# ESC-combined.net
KiCad netlist of a schematic drawn in EAGLE
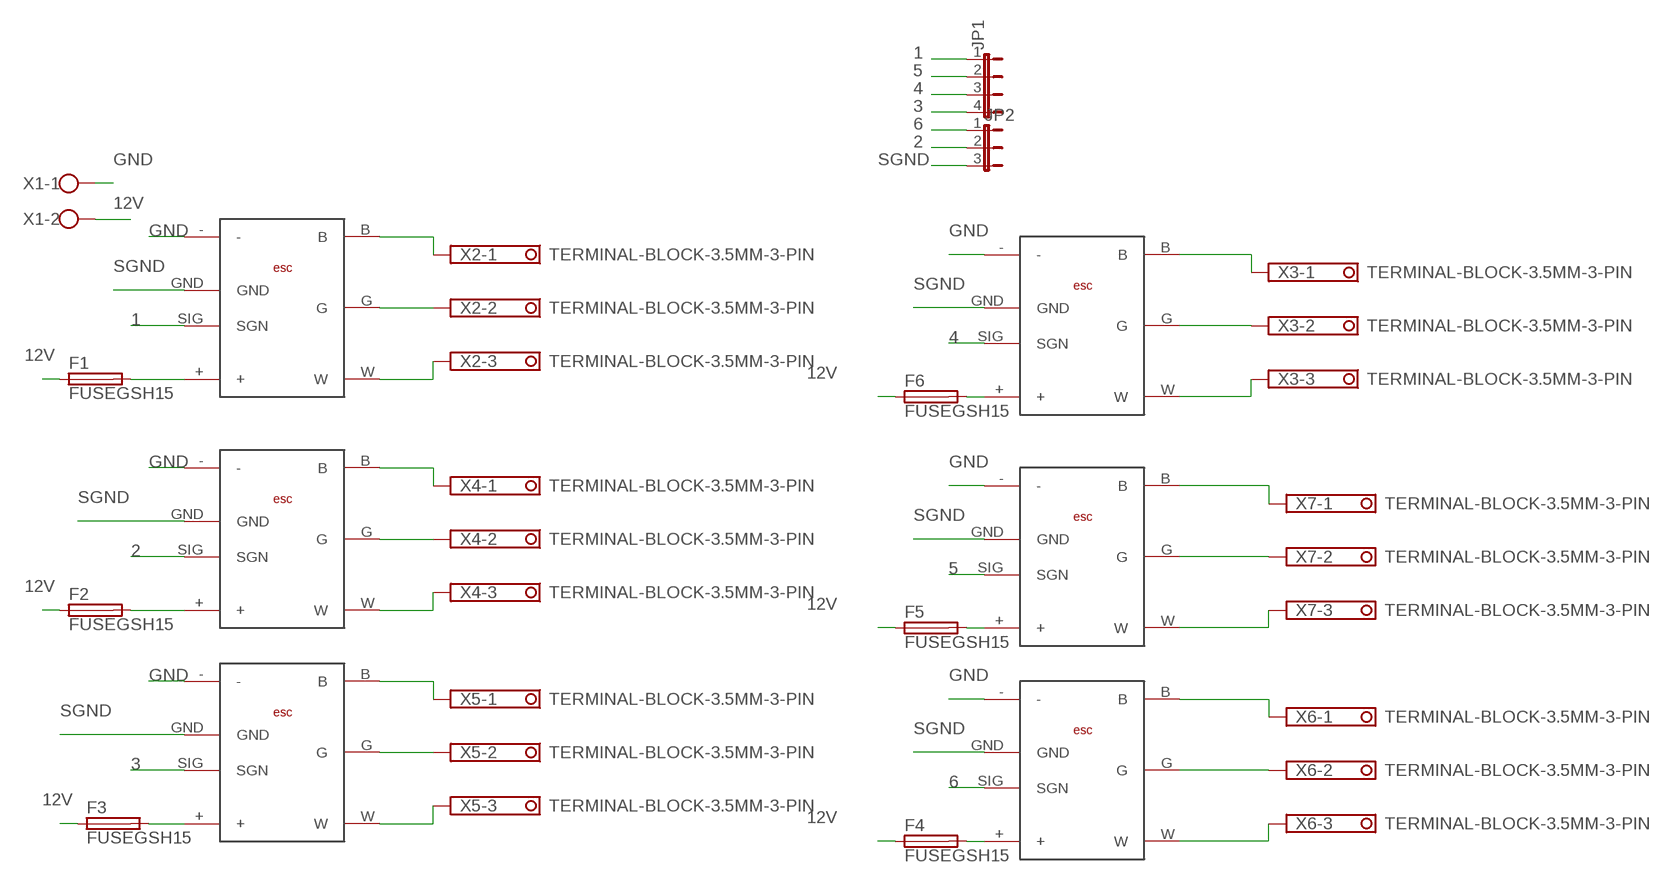
[diagram p0: schematic, sheet 1]

(export (version "E")
  (design (tool "Eeschema 10.0.6"))
  (components
    (comp (ref "F1")
      (value "FUSEGSH15")
      (footprint "eagle-import:GSH15")
      (libsource (lib "eagle-import") (part "FUSEGSH15"))
    )
    (comp (ref "F2")
      (value "FUSEGSH15")
      (footprint "eagle-import:GSH15")
      (libsource (lib "eagle-import") (part "FUSEGSH15"))
    )
    (comp (ref "F3")
      (value "FUSEGSH15")
      (footprint "eagle-import:GSH15")
      (libsource (lib "eagle-import") (part "FUSEGSH15"))
    )
    (comp (ref "F4")
      (value "FUSEGSH15")
      (footprint "eagle-import:GSH15")
      (libsource (lib "eagle-import") (part "FUSEGSH15"))
    )
    (comp (ref "F5")
      (value "FUSEGSH15")
      (footprint "eagle-import:GSH15")
      (libsource (lib "eagle-import") (part "FUSEGSH15"))
    )
    (comp (ref "F6")
      (value "FUSEGSH15")
      (footprint "eagle-import:GSH15")
      (libsource (lib "eagle-import") (part "FUSEGSH15"))
    )
    (comp (ref "JP1")
      (value "JP4E")
      (footprint "eagle-import:JP4")
      (libsource (lib "eagle-import") (part "JP4E"))
    )
    (comp (ref "JP2")
      (value "JP2E")
      (footprint "eagle-import:JP2")
      (libsource (lib "eagle-import") (part "JP2E"))
    )
    (comp (ref "U$1")
      (value "ESCV!")
      (footprint "eagle-import:ESCV!")
      (libsource (lib "eagle-import") (part "ESCV!"))
    )
    (comp (ref "U$2")
      (value "ESCV!")
      (footprint "eagle-import:ESCV!")
      (libsource (lib "eagle-import") (part "ESCV!"))
    )
    (comp (ref "U$3")
      (value "ESCV!")
      (footprint "eagle-import:ESCV!")
      (libsource (lib "eagle-import") (part "ESCV!"))
    )
    (comp (ref "U$4")
      (value "ESCV!")
      (footprint "eagle-import:ESCV!")
      (libsource (lib "eagle-import") (part "ESCV!"))
    )
    (comp (ref "U$5")
      (value "ESCV!")
      (footprint "eagle-import:ESCV!")
      (libsource (lib "eagle-import") (part "ESCV!"))
    )
    (comp (ref "U$6")
      (value "ESCV!")
      (footprint "eagle-import:ESCV!")
      (libsource (lib "eagle-import") (part "ESCV!"))
    )
    (comp (ref "X1")
      (value "12V")
      (footprint "eagle-import:W237-102")
      (fields (field (name "MPN") "237-102"))
      (libsource (lib "eagle-import") (part "W237-102"))
    )
    (comp (ref "X2")
      (value "TERMINAL-BLOCK-3.5MM-3-PIN")
      (footprint "eagle-import:HDRV3W150P950_1X3_3150X1470X1860A")
      (libsource (lib "eagle-import") (part "TERMINAL-BLOCK-3.5MM-3-PIN"))
    )
    (comp (ref "X3")
      (value "TERMINAL-BLOCK-3.5MM-3-PIN")
      (footprint "eagle-import:HDRV3W150P950_1X3_3150X1470X1860A")
      (libsource (lib "eagle-import") (part "TERMINAL-BLOCK-3.5MM-3-PIN"))
    )
    (comp (ref "X4")
      (value "TERMINAL-BLOCK-3.5MM-3-PIN")
      (footprint "eagle-import:HDRV3W150P950_1X3_3150X1470X1860A")
      (libsource (lib "eagle-import") (part "TERMINAL-BLOCK-3.5MM-3-PIN"))
    )
    (comp (ref "X5")
      (value "TERMINAL-BLOCK-3.5MM-3-PIN")
      (footprint "eagle-import:HDRV3W150P950_1X3_3150X1470X1860A")
      (libsource (lib "eagle-import") (part "TERMINAL-BLOCK-3.5MM-3-PIN"))
    )
    (comp (ref "X6")
      (value "TERMINAL-BLOCK-3.5MM-3-PIN")
      (footprint "eagle-import:HDRV3W150P950_1X3_3150X1470X1860A")
      (libsource (lib "eagle-import") (part "TERMINAL-BLOCK-3.5MM-3-PIN"))
    )
    (comp (ref "X7")
      (value "TERMINAL-BLOCK-3.5MM-3-PIN")
      (footprint "eagle-import:HDRV3W150P950_1X3_3150X1470X1860A")
      (libsource (lib "eagle-import") (part "TERMINAL-BLOCK-3.5MM-3-PIN"))
    )
  )
  (nets
    (net (code "1") (name "/1") (class "Default")
      (node (ref "JP1") (pin "1") (pinfunction "1_1") (pintype "passive"))
      (node (ref "U$1") (pin "SIG") (pinfunction "SGN_SIG") (pintype "bidirectional"))
    )
    (net (code "2") (name "/2") (class "Default")
      (node (ref "JP2") (pin "2") (pinfunction "2_2") (pintype "passive"))
      (node (ref "U$2") (pin "SIG") (pinfunction "SGN_SIG") (pintype "bidirectional"))
    )
    (net (code "3") (name "/3") (class "Default")
      (node (ref "JP1") (pin "4") (pinfunction "4_4") (pintype "passive"))
      (node (ref "U$3") (pin "SIG") (pinfunction "SGN_SIG") (pintype "bidirectional"))
    )
    (net (code "4") (name "/4") (class "Default")
      (node (ref "JP1") (pin "3") (pinfunction "3_3") (pintype "passive"))
      (node (ref "U$4") (pin "SIG") (pinfunction "SGN_SIG") (pintype "bidirectional"))
    )
    (net (code "5") (name "/5") (class "Default")
      (node (ref "JP1") (pin "2") (pinfunction "2_2") (pintype "passive"))
      (node (ref "U$5") (pin "SIG") (pinfunction "SGN_SIG") (pintype "bidirectional"))
    )
    (net (code "6") (name "/6") (class "Default")
      (node (ref "JP2") (pin "1") (pinfunction "1_1") (pintype "passive"))
      (node (ref "U$6") (pin "SIG") (pinfunction "SGN_SIG") (pintype "bidirectional"))
    )
    (net (code "7") (name "/12V") (class "Default")
      (node (ref "F1") (pin "1") (pinfunction "1_1") (pintype "passive"))
      (node (ref "F2") (pin "1") (pinfunction "1_1") (pintype "passive"))
      (node (ref "F3") (pin "1") (pinfunction "1_1") (pintype "passive"))
      (node (ref "F4") (pin "1") (pinfunction "1_1") (pintype "passive"))
      (node (ref "F5") (pin "1") (pinfunction "1_1") (pintype "passive"))
      (node (ref "F6") (pin "1") (pinfunction "1_1") (pintype "passive"))
      (node (ref "X1") (pin "2") (pinfunction "KL_2") (pintype "passive"))
    )
    (net (code "8") (name "/GND") (class "Default")
      (node (ref "U$1") (pin "-") (pinfunction "-_-") (pintype "bidirectional"))
      (node (ref "U$2") (pin "-") (pinfunction "-_-") (pintype "bidirectional"))
      (node (ref "U$3") (pin "-") (pinfunction "-_-") (pintype "bidirectional"))
      (node (ref "U$4") (pin "-") (pinfunction "-_-") (pintype "bidirectional"))
      (node (ref "U$5") (pin "-") (pinfunction "-_-") (pintype "bidirectional"))
      (node (ref "U$6") (pin "-") (pinfunction "-_-") (pintype "bidirectional"))
      (node (ref "X1") (pin "1") (pinfunction "KL_1") (pintype "passive"))
    )
    (net (code "9") (name "/SGND") (class "Default")
      (node (ref "JP2") (pin "3") (pinfunction "3_3") (pintype "passive"))
      (node (ref "U$1") (pin "GND") (pinfunction "GND_GND") (pintype "bidirectional"))
      (node (ref "U$2") (pin "GND") (pinfunction "GND_GND") (pintype "bidirectional"))
      (node (ref "U$3") (pin "GND") (pinfunction "GND_GND") (pintype "bidirectional"))
      (node (ref "U$4") (pin "GND") (pinfunction "GND_GND") (pintype "bidirectional"))
      (node (ref "U$5") (pin "GND") (pinfunction "GND_GND") (pintype "bidirectional"))
      (node (ref "U$6") (pin "GND") (pinfunction "GND_GND") (pintype "bidirectional"))
    )
    (net (code "10") (name "Net-(F1-Pad2)") (class "Default")
      (node (ref "F1") (pin "2") (pinfunction "2_2") (pintype "passive"))
      (node (ref "U$1") (pin "+") (pinfunction "+_+") (pintype "bidirectional"))
    )
    (net (code "11") (name "Net-(F2-Pad2)") (class "Default")
      (node (ref "F2") (pin "2") (pinfunction "2_2") (pintype "passive"))
      (node (ref "U$2") (pin "+") (pinfunction "+_+") (pintype "bidirectional"))
    )
    (net (code "12") (name "Net-(F3-Pad2)") (class "Default")
      (node (ref "F3") (pin "2") (pinfunction "2_2") (pintype "passive"))
      (node (ref "U$3") (pin "+") (pinfunction "+_+") (pintype "bidirectional"))
    )
    (net (code "13") (name "Net-(F4-Pad2)") (class "Default")
      (node (ref "F4") (pin "2") (pinfunction "2_2") (pintype "passive"))
      (node (ref "U$6") (pin "+") (pinfunction "+_+") (pintype "bidirectional"))
    )
    (net (code "14") (name "Net-(F5-Pad2)") (class "Default")
      (node (ref "F5") (pin "2") (pinfunction "2_2") (pintype "passive"))
      (node (ref "U$5") (pin "+") (pinfunction "+_+") (pintype "bidirectional"))
    )
    (net (code "15") (name "Net-(F6-Pad2)") (class "Default")
      (node (ref "F6") (pin "2") (pinfunction "2_2") (pintype "passive"))
      (node (ref "U$4") (pin "+") (pinfunction "+_+") (pintype "bidirectional"))
    )
    (net (code "16") (name "Net-(X2A-K)") (class "Default")
      (node (ref "U$1") (pin "B") (pinfunction "B_B") (pintype "bidirectional"))
      (node (ref "X2") (pin "1") (pinfunction "K_1") (pintype "passive"))
    )
    (net (code "17") (name "Net-(X2B-K)") (class "Default")
      (node (ref "U$1") (pin "G") (pinfunction "G_G") (pintype "bidirectional"))
      (node (ref "X2") (pin "2") (pinfunction "K_2") (pintype "passive"))
    )
    (net (code "18") (name "Net-(X2C-K)") (class "Default")
      (node (ref "U$1") (pin "W") (pinfunction "W_W") (pintype "bidirectional"))
      (node (ref "X2") (pin "3") (pinfunction "K_3") (pintype "passive"))
    )
    (net (code "19") (name "Net-(X3A-K)") (class "Default")
      (node (ref "U$4") (pin "B") (pinfunction "B_B") (pintype "bidirectional"))
      (node (ref "X3") (pin "1") (pinfunction "K_1") (pintype "passive"))
    )
    (net (code "20") (name "Net-(X3B-K)") (class "Default")
      (node (ref "U$4") (pin "G") (pinfunction "G_G") (pintype "bidirectional"))
      (node (ref "X3") (pin "2") (pinfunction "K_2") (pintype "passive"))
    )
    (net (code "21") (name "Net-(X3C-K)") (class "Default")
      (node (ref "U$4") (pin "W") (pinfunction "W_W") (pintype "bidirectional"))
      (node (ref "X3") (pin "3") (pinfunction "K_3") (pintype "passive"))
    )
    (net (code "22") (name "Net-(X4A-K)") (class "Default")
      (node (ref "U$2") (pin "B") (pinfunction "B_B") (pintype "bidirectional"))
      (node (ref "X4") (pin "1") (pinfunction "K_1") (pintype "passive"))
    )
    (net (code "23") (name "Net-(X4B-K)") (class "Default")
      (node (ref "U$2") (pin "G") (pinfunction "G_G") (pintype "bidirectional"))
      (node (ref "X4") (pin "2") (pinfunction "K_2") (pintype "passive"))
    )
    (net (code "24") (name "Net-(X4C-K)") (class "Default")
      (node (ref "U$2") (pin "W") (pinfunction "W_W") (pintype "bidirectional"))
      (node (ref "X4") (pin "3") (pinfunction "K_3") (pintype "passive"))
    )
    (net (code "25") (name "Net-(X5A-K)") (class "Default")
      (node (ref "U$3") (pin "B") (pinfunction "B_B") (pintype "bidirectional"))
      (node (ref "X5") (pin "1") (pinfunction "K_1") (pintype "passive"))
    )
    (net (code "26") (name "Net-(X5B-K)") (class "Default")
      (node (ref "U$3") (pin "G") (pinfunction "G_G") (pintype "bidirectional"))
      (node (ref "X5") (pin "2") (pinfunction "K_2") (pintype "passive"))
    )
    (net (code "27") (name "Net-(X5C-K)") (class "Default")
      (node (ref "U$3") (pin "W") (pinfunction "W_W") (pintype "bidirectional"))
      (node (ref "X5") (pin "3") (pinfunction "K_3") (pintype "passive"))
    )
    (net (code "28") (name "Net-(X6A-K)") (class "Default")
      (node (ref "U$6") (pin "B") (pinfunction "B_B") (pintype "bidirectional"))
      (node (ref "X6") (pin "1") (pinfunction "K_1") (pintype "passive"))
    )
    (net (code "29") (name "Net-(X6B-K)") (class "Default")
      (node (ref "U$6") (pin "G") (pinfunction "G_G") (pintype "bidirectional"))
      (node (ref "X6") (pin "2") (pinfunction "K_2") (pintype "passive"))
    )
    (net (code "30") (name "Net-(X6C-K)") (class "Default")
      (node (ref "U$6") (pin "W") (pinfunction "W_W") (pintype "bidirectional"))
      (node (ref "X6") (pin "3") (pinfunction "K_3") (pintype "passive"))
    )
    (net (code "31") (name "Net-(X7A-K)") (class "Default")
      (node (ref "U$5") (pin "B") (pinfunction "B_B") (pintype "bidirectional"))
      (node (ref "X7") (pin "1") (pinfunction "K_1") (pintype "passive"))
    )
    (net (code "32") (name "Net-(X7B-K)") (class "Default")
      (node (ref "U$5") (pin "G") (pinfunction "G_G") (pintype "bidirectional"))
      (node (ref "X7") (pin "2") (pinfunction "K_2") (pintype "passive"))
    )
    (net (code "33") (name "Net-(X7C-K)") (class "Default")
      (node (ref "U$5") (pin "W") (pinfunction "W_W") (pintype "bidirectional"))
      (node (ref "X7") (pin "3") (pinfunction "K_3") (pintype "passive"))
    )
  )
)
